# RTI-Dome-eth-RP2040_V2.net
KiCad netlist of a schematic drawn in EAGLE
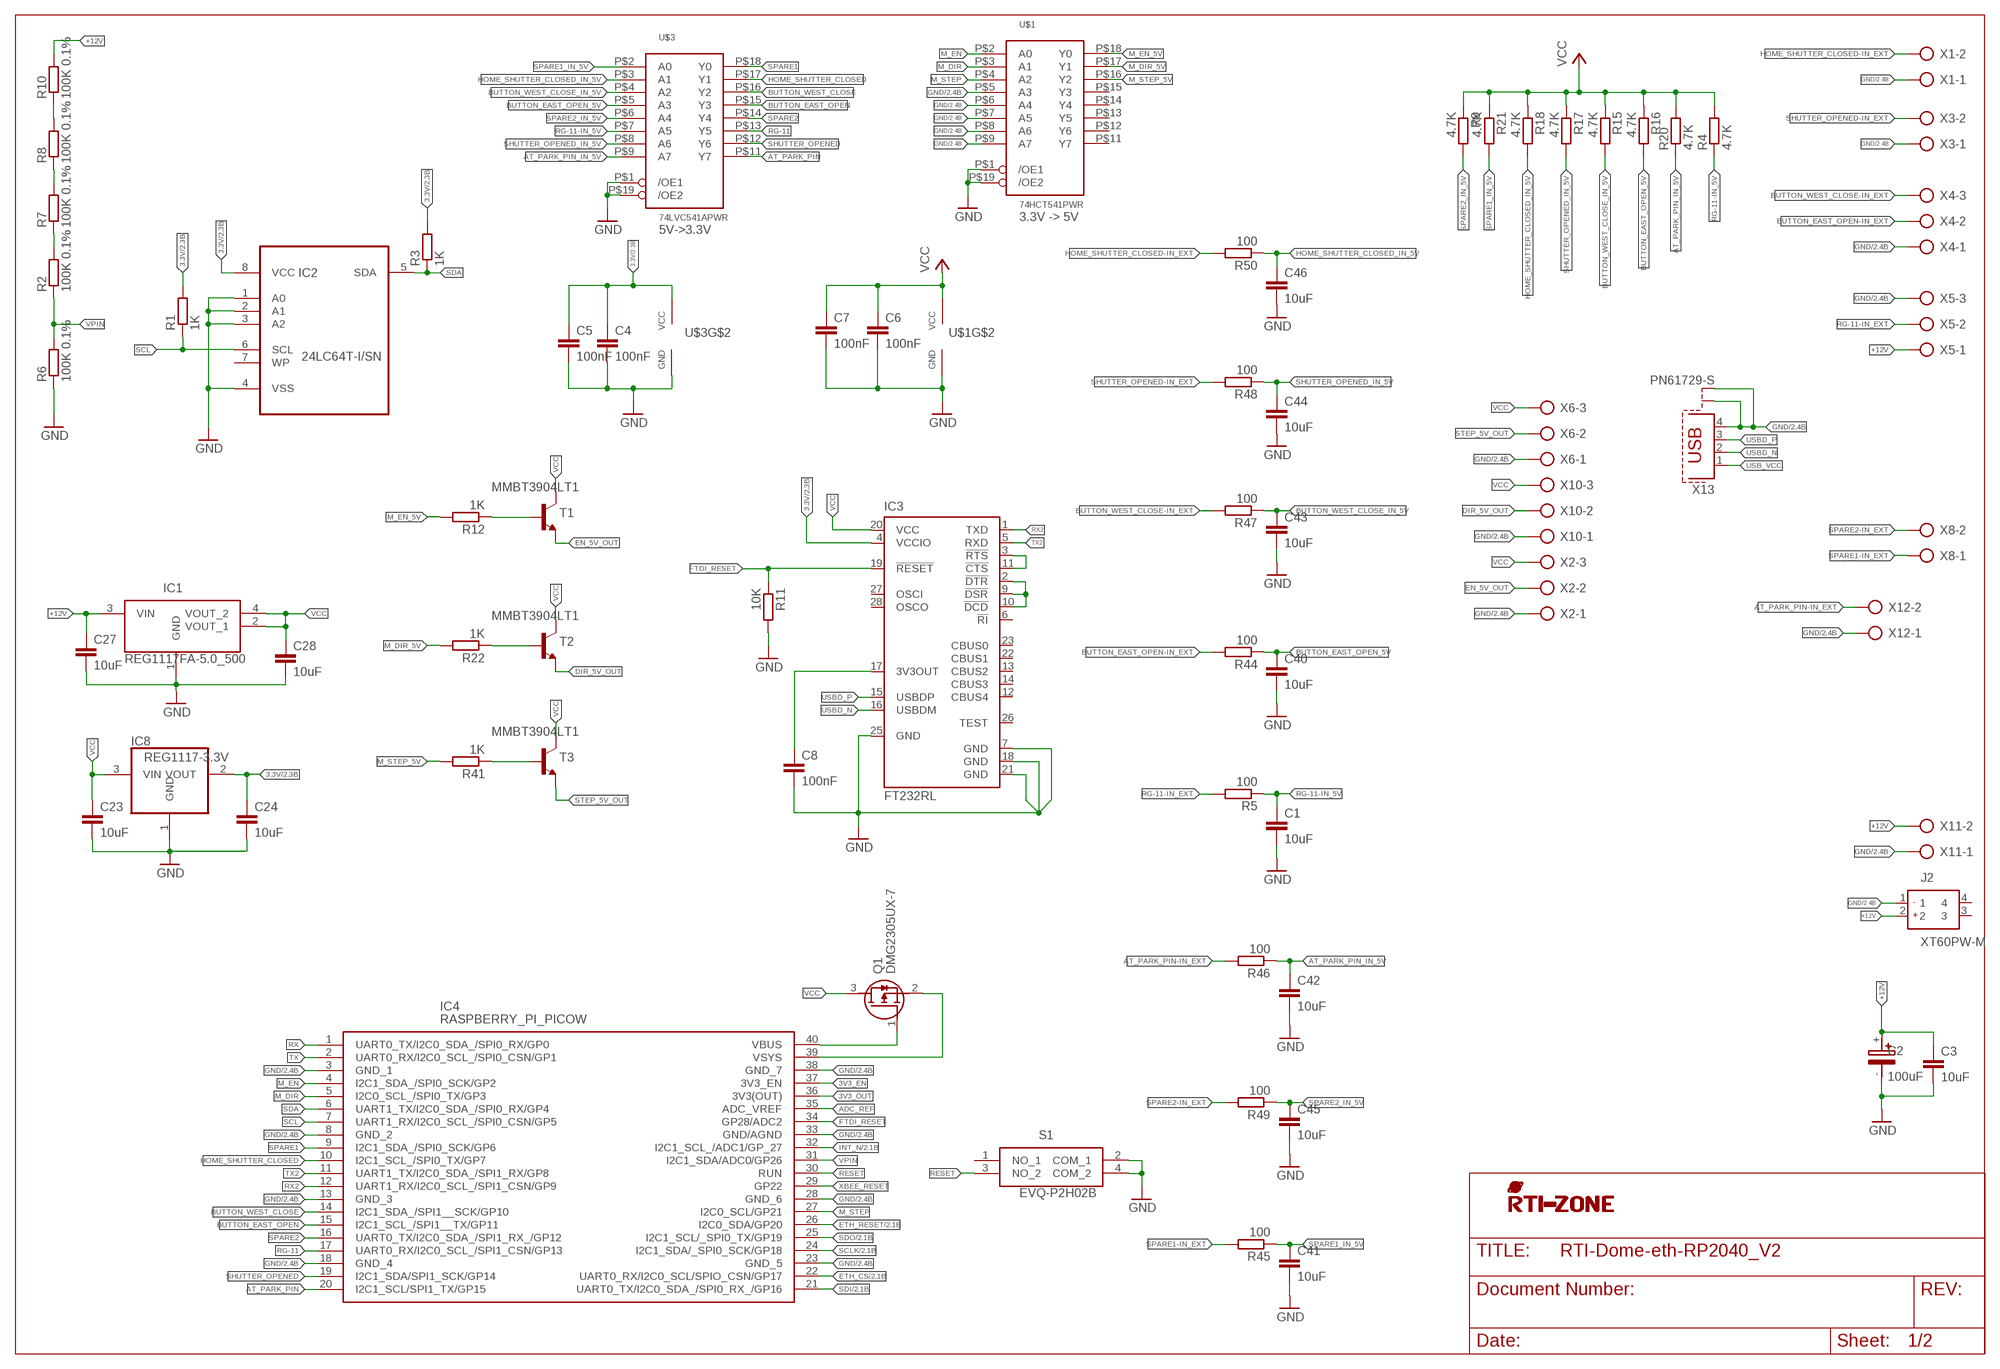
[diagram p0: schematic, sheet 1]
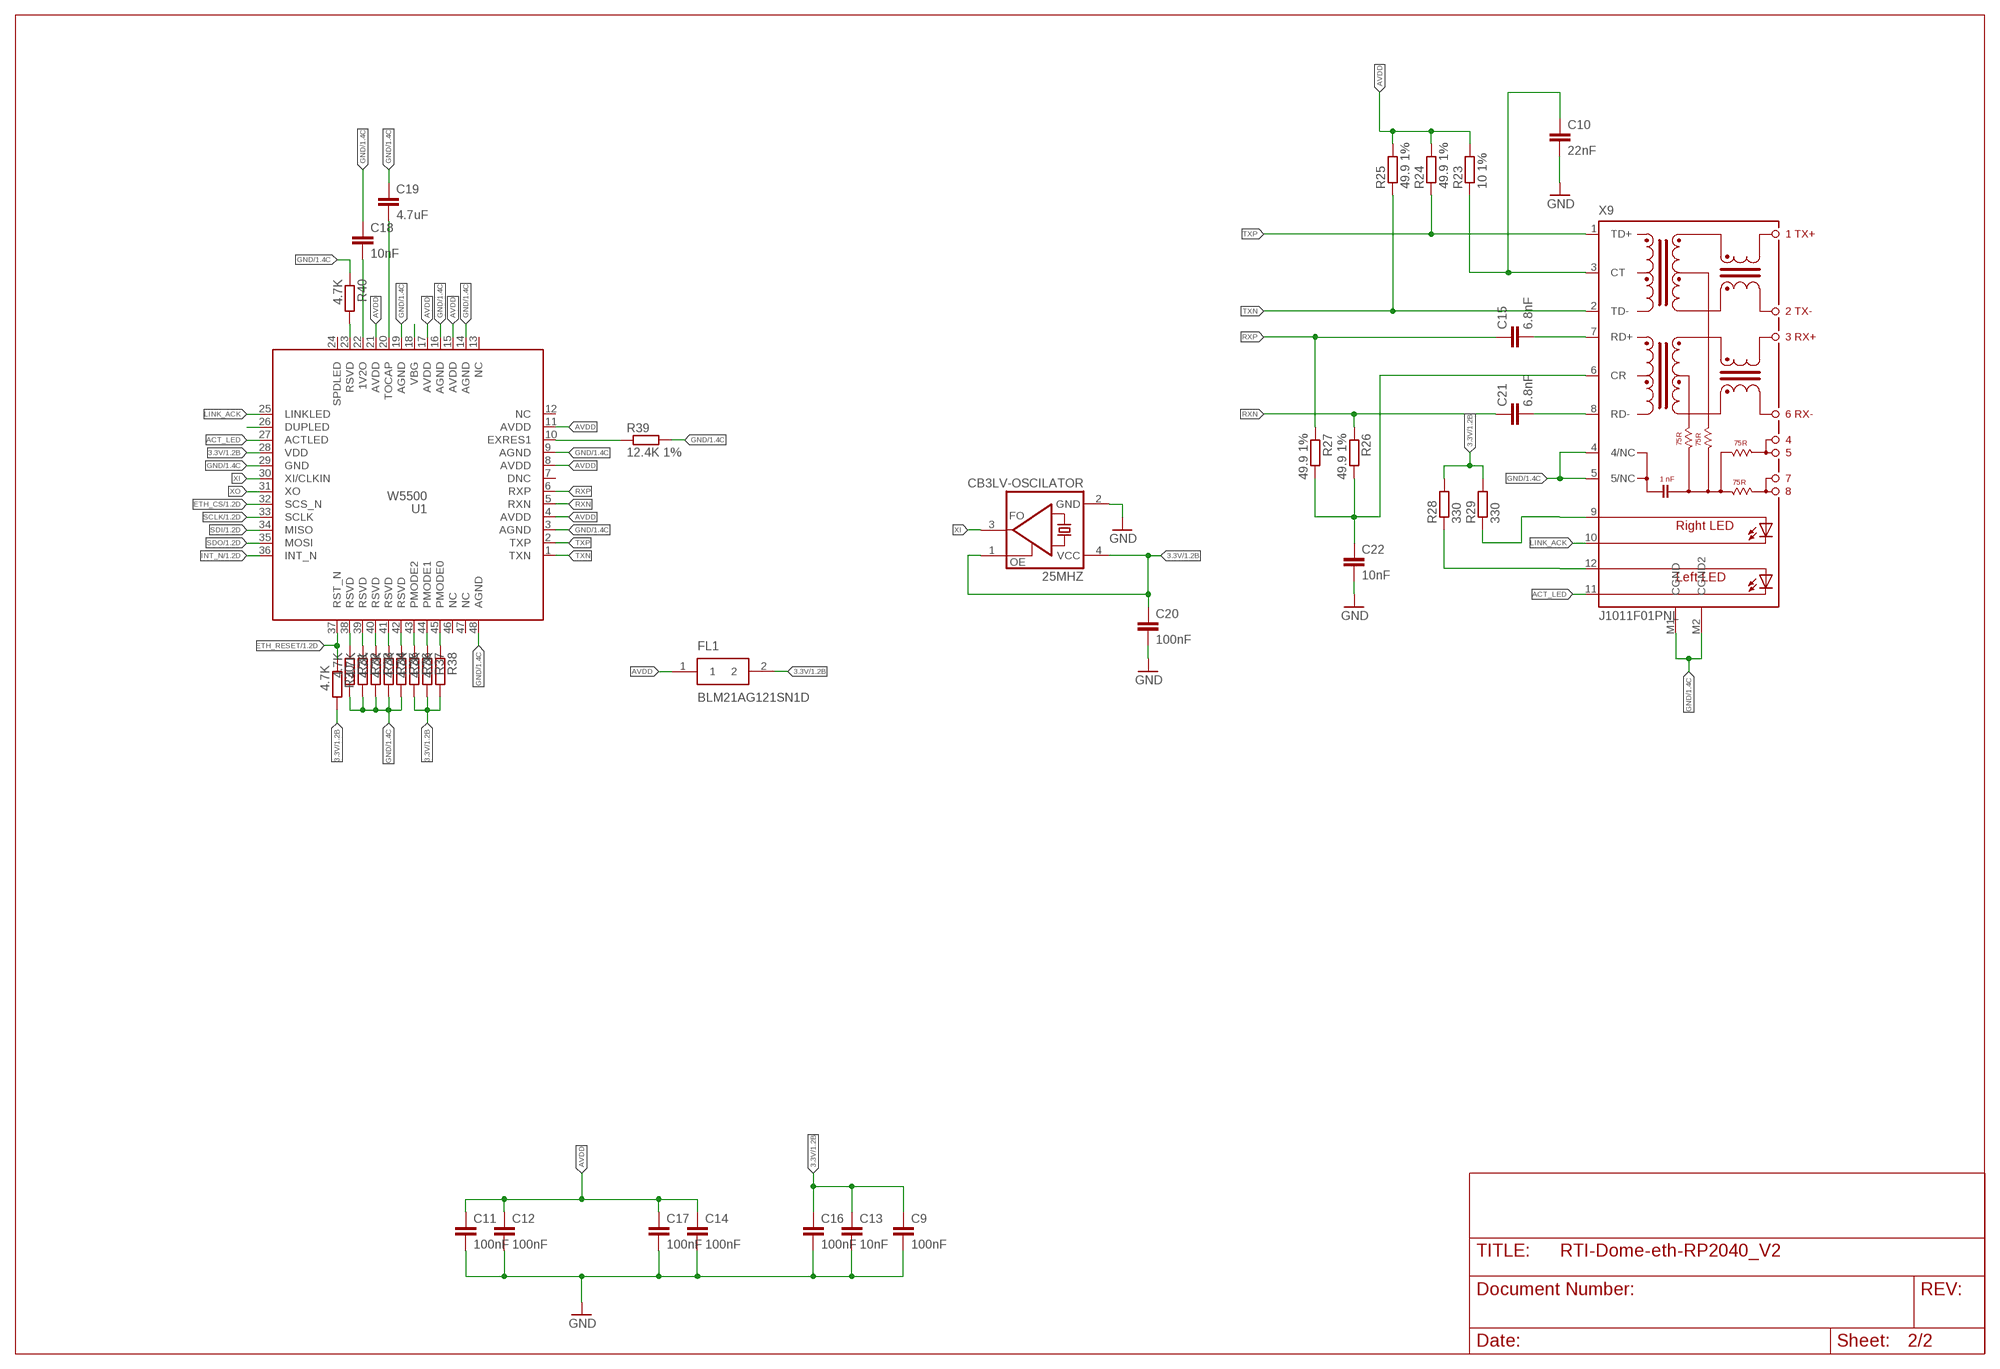
[diagram p1: schematic, sheet 2]

(export (version "E")
  (design (tool "Eeschema 10.0.6"))
  (components
    (comp (ref "C1")
      (value "10uF")
      (footprint "eagle-import:C0603")
      (fields (field (name "MPN") "CC0805KKX5R8BB106"))
      (libsource (lib "eagle-import") (part "C-EUC0603"))
    )
    (comp (ref "C2")
      (value "100uF")
      (footprint "eagle-import:UD-10X10_NICHICON")
      (fields (field (name "MPN") "MAL215099804E3"))
      (libsource (lib "eagle-import") (part "MAL215099804E3{dblquote}{dblquote}"))
    )
    (comp (ref "C3")
      (value "10uF")
      (footprint "eagle-import:C0603")
      (fields (field (name "MPN") "CC0805KKX5R8BB106"))
      (libsource (lib "eagle-import") (part "C-EUC0603"))
    )
    (comp (ref "C4")
      (value "100nF")
      (footprint "eagle-import:C0603")
      (fields (field (name "MPN") "0805YD104KAT2A"))
      (libsource (lib "eagle-import") (part "C-EUC0603"))
    )
    (comp (ref "C5")
      (value "100nF")
      (footprint "eagle-import:C0603")
      (fields (field (name "MPN") "0805YD104KAT2A"))
      (libsource (lib "eagle-import") (part "C-EUC0603"))
    )
    (comp (ref "C6")
      (value "100nF")
      (footprint "eagle-import:C0603")
      (fields (field (name "MPN") "0805YD104KAT2A"))
      (libsource (lib "eagle-import") (part "C-EUC0603"))
    )
    (comp (ref "C7")
      (value "100nF")
      (footprint "eagle-import:C0603")
      (fields (field (name "MPN") "0805YD104KAT2A"))
      (libsource (lib "eagle-import") (part "C-EUC0603"))
    )
    (comp (ref "C8")
      (value "100nF")
      (footprint "eagle-import:C0603")
      (fields (field (name "MPN") "0805YD104KAT2A"))
      (libsource (lib "eagle-import") (part "C-EUC0603"))
    )
    (comp (ref "C23")
      (value "10uF")
      (footprint "eagle-import:C0603")
      (fields (field (name "MPN") "CC0805KKX5R8BB106"))
      (libsource (lib "eagle-import") (part "C-EUC0603"))
    )
    (comp (ref "C24")
      (value "10uF")
      (footprint "eagle-import:C0603")
      (fields (field (name "MPN") "CC0805KKX5R8BB106"))
      (libsource (lib "eagle-import") (part "C-EUC0603"))
    )
    (comp (ref "C27")
      (value "10uF")
      (footprint "eagle-import:C0603")
      (fields (field (name "MPN") "CC0805KKX5R8BB106"))
      (libsource (lib "eagle-import") (part "C-EUC0603"))
    )
    (comp (ref "C28")
      (value "10uF")
      (footprint "eagle-import:C0603")
      (fields (field (name "MPN") "CC0805KKX5R8BB106"))
      (libsource (lib "eagle-import") (part "C-EUC0603"))
    )
    (comp (ref "C40")
      (value "10uF")
      (footprint "eagle-import:C0603")
      (fields (field (name "MPN") "CC0805KKX5R8BB106"))
      (libsource (lib "eagle-import") (part "C-EUC0603"))
    )
    (comp (ref "C41")
      (value "10uF")
      (footprint "eagle-import:C0603")
      (fields (field (name "MPN") "CC0805KKX5R8BB106"))
      (libsource (lib "eagle-import") (part "C-EUC0603"))
    )
    (comp (ref "C42")
      (value "10uF")
      (footprint "eagle-import:C0603")
      (fields (field (name "MPN") "CC0805KKX5R8BB106"))
      (libsource (lib "eagle-import") (part "C-EUC0603"))
    )
    (comp (ref "C43")
      (value "10uF")
      (footprint "eagle-import:C0603")
      (fields (field (name "MPN") "CC0805KKX5R8BB106"))
      (libsource (lib "eagle-import") (part "C-EUC0603"))
    )
    (comp (ref "C44")
      (value "10uF")
      (footprint "eagle-import:C0603")
      (fields (field (name "MPN") "CC0805KKX5R8BB106"))
      (libsource (lib "eagle-import") (part "C-EUC0603"))
    )
    (comp (ref "C45")
      (value "10uF")
      (footprint "eagle-import:C0603")
      (fields (field (name "MPN") "CC0805KKX5R8BB106"))
      (libsource (lib "eagle-import") (part "C-EUC0603"))
    )
    (comp (ref "C46")
      (value "10uF")
      (footprint "eagle-import:C0603")
      (fields (field (name "MPN") "CC0805KKX5R8BB106"))
      (libsource (lib "eagle-import") (part "C-EUC0603"))
    )
    (comp (ref "IC1")
      (value "REG1117FA-5.0_500")
      (footprint "eagle-import:REG1117FA50500")
      (fields
        (field (name "ARROW_PART_NUMBER") "REG1117FA-5.0/500")
        (field (name "MOUSER_PART_NUMBER") "595-REG1117FA50/500")
      )
      (libsource (lib "eagle-import") (part "REG1117FA-5.0_500"))
    )
    (comp (ref "IC2")
      (value "24LC64T-I/SN")
      (footprint "eagle-import:SOIC127P600X175-8N")
      (libsource (lib "eagle-import") (part "24LC64T-I/SN"))
    )
    (comp (ref "IC3")
      (value "FT232RL")
      (footprint "eagle-import:SSOP28")
      (fields (field (name "MPN") "FT232RL-REEL"))
      (libsource (lib "eagle-import") (part "FT232RL"))
    )
    (comp (ref "IC4")
      (value "RASPBERRY_PI_PICOW")
      (footprint "eagle-import:RASPBERRYPIPICO-W")
      (libsource (lib "eagle-import") (part "RASPBERRY_PI_PICOW"))
    )
    (comp (ref "IC8")
      (value "REG1117-3.3V")
      (footprint "eagle-import:SOT223")
      (fields (field (name "MPN") "REG1117") (field (name "MPN_1") "REG1117-3.3/2K5"))
      (libsource (lib "eagle-import") (part "REG1117"))
    )
    (comp (ref "J2")
      (value "XT60PW-M")
      (footprint "eagle-import:XT60PWM")
      (libsource (lib "eagle-import") (part "XT60PW-M"))
    )
    (comp (ref "Q1")
      (value "DMG2305UX-7")
      (footprint "eagle-import:SOT96P240X115-3N")
      (fields (field (name "MOUSER_PART_NUMBER") "621-DMG2305UX-7"))
      (libsource (lib "eagle-import") (part "DMG2305UX-7"))
    )
    (comp (ref "R1")
      (value "1K")
      (footprint "eagle-import:R0603")
      (fields (field (name "MPN") "RT0805FRE071KL"))
      (libsource (lib "eagle-import") (part "R-EU_R0603"))
    )
    (comp (ref "R2")
      (value "100K 0.1%")
      (footprint "eagle-import:R0603")
      (fields (field (name "MPN") "AT0805BRD07100KL"))
      (libsource (lib "eagle-import") (part "R-EU_R0603"))
    )
    (comp (ref "R3")
      (value "1K")
      (footprint "eagle-import:R0603")
      (fields (field (name "MPN") "RT0805FRE071KL"))
      (libsource (lib "eagle-import") (part "R-EU_R0603"))
    )
    (comp (ref "R4")
      (value "4.7K")
      (footprint "eagle-import:R0603")
      (fields (field (name "MPN") "RT0805FRE074K7L"))
      (libsource (lib "eagle-import") (part "R-EU_R0603"))
    )
    (comp (ref "R5")
      (value "100")
      (footprint "eagle-import:R0603")
      (fields (field (name "MPN") "RT0805FRD07100RL"))
      (libsource (lib "eagle-import") (part "R-EU_R0603"))
    )
    (comp (ref "R6")
      (value "100K 0.1%")
      (footprint "eagle-import:R0603")
      (fields (field (name "MPN") "AT0805BRD07100KL"))
      (libsource (lib "eagle-import") (part "R-EU_R0603"))
    )
    (comp (ref "R7")
      (value "100K 0.1%")
      (footprint "eagle-import:R0603")
      (fields (field (name "MPN") "AT0805BRD07100KL"))
      (libsource (lib "eagle-import") (part "R-EU_R0603"))
    )
    (comp (ref "R8")
      (value "100K 0.1%")
      (footprint "eagle-import:R0603")
      (fields (field (name "MPN") "AT0805BRD07100KL"))
      (libsource (lib "eagle-import") (part "R-EU_R0603"))
    )
    (comp (ref "R9")
      (value "4.7K")
      (footprint "eagle-import:R0603")
      (fields (field (name "MPN") "RT0805FRE074K7L"))
      (libsource (lib "eagle-import") (part "R-EU_R0603"))
    )
    (comp (ref "R10")
      (value "100K 0.1%")
      (footprint "eagle-import:R0603")
      (fields (field (name "MPN") "AT0805BRD07100KL"))
      (libsource (lib "eagle-import") (part "R-EU_R0603"))
    )
    (comp (ref "R11")
      (value "10K")
      (footprint "eagle-import:R0603")
      (fields (field (name "MPN") "RT0805FRE0710KL"))
      (libsource (lib "eagle-import") (part "R-EU_R0603"))
    )
    (comp (ref "R12")
      (value "1K")
      (footprint "eagle-import:R0603")
      (fields (field (name "MPN") "RT0805FRE074K7L"))
      (libsource (lib "eagle-import") (part "R-EU_R0603"))
    )
    (comp (ref "R15")
      (value "4.7K")
      (footprint "eagle-import:R0603")
      (fields (field (name "MPN") "RT0805FRE074K7L"))
      (libsource (lib "eagle-import") (part "R-EU_R0603"))
    )
    (comp (ref "R16")
      (value "4.7K")
      (footprint "eagle-import:R0603")
      (fields (field (name "MPN") "RT0805FRE074K7L"))
      (libsource (lib "eagle-import") (part "R-EU_R0603"))
    )
    (comp (ref "R17")
      (value "4.7K")
      (footprint "eagle-import:R0603")
      (fields (field (name "MPN") "RT0805FRE074K7L"))
      (libsource (lib "eagle-import") (part "R-EU_R0603"))
    )
    (comp (ref "R18")
      (value "4.7K")
      (footprint "eagle-import:R0603")
      (fields (field (name "MPN") "RT0805FRE074K7L"))
      (libsource (lib "eagle-import") (part "R-EU_R0603"))
    )
    (comp (ref "R20")
      (value "4.7K")
      (footprint "eagle-import:R0603")
      (fields (field (name "MPN") "RT0805FRE074K7L"))
      (libsource (lib "eagle-import") (part "R-EU_R0603"))
    )
    (comp (ref "R21")
      (value "4.7K")
      (footprint "eagle-import:R0603")
      (fields (field (name "MPN") "RT0805FRE074K7L"))
      (libsource (lib "eagle-import") (part "R-EU_R0603"))
    )
    (comp (ref "R22")
      (value "1K")
      (footprint "eagle-import:R0603")
      (fields (field (name "MPN") "RT0805FRE074K7L"))
      (libsource (lib "eagle-import") (part "R-EU_R0603"))
    )
    (comp (ref "R41")
      (value "1K")
      (footprint "eagle-import:R0603")
      (fields (field (name "MPN") "RT0805FRE074K7L"))
      (libsource (lib "eagle-import") (part "R-EU_R0603"))
    )
    (comp (ref "R44")
      (value "100")
      (footprint "eagle-import:R0603")
      (fields (field (name "MPN") "RT0805FRD07100RL"))
      (libsource (lib "eagle-import") (part "R-EU_R0603"))
    )
    (comp (ref "R45")
      (value "100")
      (footprint "eagle-import:R0603")
      (fields (field (name "MPN") "RT0805FRD07100RL"))
      (libsource (lib "eagle-import") (part "R-EU_R0603"))
    )
    (comp (ref "R46")
      (value "100")
      (footprint "eagle-import:R0603")
      (fields (field (name "MPN") "RT0805FRD07100RL"))
      (libsource (lib "eagle-import") (part "R-EU_R0603"))
    )
    (comp (ref "R47")
      (value "100")
      (footprint "eagle-import:R0603")
      (fields (field (name "MPN") "RT0805FRD07100RL"))
      (libsource (lib "eagle-import") (part "R-EU_R0603"))
    )
    (comp (ref "R48")
      (value "100")
      (footprint "eagle-import:R0603")
      (fields (field (name "MPN") "RT0805FRD07100RL"))
      (libsource (lib "eagle-import") (part "R-EU_R0603"))
    )
    (comp (ref "R49")
      (value "100")
      (footprint "eagle-import:R0603")
      (fields (field (name "MPN") "RT0805FRD07100RL"))
      (libsource (lib "eagle-import") (part "R-EU_R0603"))
    )
    (comp (ref "R50")
      (value "100")
      (footprint "eagle-import:R0603")
      (fields (field (name "MPN") "RT0805FRD07100RL"))
      (libsource (lib "eagle-import") (part "R-EU_R0603"))
    )
    (comp (ref "S1")
      (value "EVQ-P2H02B")
      (footprint "eagle-import:EVQP2H02B")
      (fields (field (name "MOUSER_PART_NUMBER") "667-EVQ-P2H02B"))
      (libsource (lib "eagle-import") (part "EVQ-P2H02B"))
    )
    (comp (ref "T1")
      (value "MMBT3904LT1")
      (footprint "eagle-import:SOT23")
      (libsource (lib "eagle-import") (part "MMBT3904LT1"))
    )
    (comp (ref "T2")
      (value "MMBT3904LT1")
      (footprint "eagle-import:SOT23")
      (libsource (lib "eagle-import") (part "MMBT3904LT1"))
    )
    (comp (ref "T3")
      (value "MMBT3904LT1")
      (footprint "eagle-import:SOT23")
      (libsource (lib "eagle-import") (part "MMBT3904LT1"))
    )
    (comp (ref "U$1")
      (value "74HCT541PWR")
      (footprint "eagle-import:TSSOP20")
      (libsource (lib "eagle-import") (part "74541B"))
    )
    (comp (ref "U$3")
      (value "74LVC541APWR")
      (footprint "eagle-import:TSSOP20")
      (libsource (lib "eagle-import") (part "74541B"))
    )
    (comp (ref "U$4")
      (value "RTI-LOGO_BIG")
      (footprint "eagle-import:LOGO_BIG")
      (libsource (lib "eagle-import") (part "RTI-LOGO_BIG"))
    )
    (comp (ref "X1")
      (value "AK500/2")
      (footprint "eagle-import:AK500_2")
      (fields (field (name "MPN") "691101710002"))
      (libsource (lib "eagle-import") (part "AK500/2"))
    )
    (comp (ref "X2")
      (value "AK500/3")
      (footprint "eagle-import:AK500_3")
      (libsource (lib "eagle-import") (part "AK500/3"))
    )
    (comp (ref "X3")
      (value "AK500/2")
      (footprint "eagle-import:AK500_2")
      (fields (field (name "MPN") "691101710002"))
      (libsource (lib "eagle-import") (part "AK500/2"))
    )
    (comp (ref "X4")
      (value "AK500/3")
      (footprint "eagle-import:AK500_3")
      (fields (field (name "MPN") "691101710003"))
      (libsource (lib "eagle-import") (part "AK500/3"))
    )
    (comp (ref "X5")
      (value "AK500/3")
      (footprint "eagle-import:AK500_3")
      (fields (field (name "MPN") "691101710003"))
      (libsource (lib "eagle-import") (part "AK500/3"))
    )
    (comp (ref "X6")
      (value "AK500/3")
      (footprint "eagle-import:AK500_3")
      (libsource (lib "eagle-import") (part "AK500/3"))
    )
    (comp (ref "X8")
      (value "AK500/2")
      (footprint "eagle-import:AK500_2")
      (fields (field (name "MPN") "691101710002"))
      (libsource (lib "eagle-import") (part "AK500/2"))
    )
    (comp (ref "X10")
      (value "AK500/3")
      (footprint "eagle-import:AK500_3")
      (libsource (lib "eagle-import") (part "AK500/3"))
    )
    (comp (ref "X11")
      (value "AK500/2")
      (footprint "eagle-import:AK500_2")
      (fields (field (name "MPN") "691101710002"))
      (libsource (lib "eagle-import") (part "AK500/2"))
    )
    (comp (ref "X12")
      (value "AK500/2")
      (footprint "eagle-import:AK500_2")
      (fields (field (name "MPN") "691101710002"))
      (libsource (lib "eagle-import") (part "AK500/2"))
    )
    (comp (ref "X13")
      (value "PN61729-S")
      (footprint "eagle-import:PN61729-S")
      (fields (field (name "MPN") "SS-52300-001"))
      (libsource (lib "eagle-import") (part "PN61729-S"))
    )
    (comp (ref "25MHZ")
      (value "CB3LV-OSCILATOR")
      (footprint "eagle-import:SMD-7050_4P")
      (fields (field (name "MPN") "CB3LV-3I-25M0000"))
      (libsource (lib "eagle-import") (part "CB3LV-OSCILATOR"))
    )
    (comp (ref "C9")
      (value "100nF")
      (footprint "eagle-import:C0603")
      (fields (field (name "MPN") "0805YD104KAT2A"))
      (libsource (lib "eagle-import") (part "C-EUC0603"))
    )
    (comp (ref "C10")
      (value "22nF")
      (footprint "eagle-import:C0603")
      (fields (field (name "MPN") "CC0805JRX7R8BB223"))
      (libsource (lib "eagle-import") (part "C-EUC0603"))
    )
    (comp (ref "C11")
      (value "100nF")
      (footprint "eagle-import:C0603")
      (fields (field (name "MPN") "0805YD104KAT2A"))
      (libsource (lib "eagle-import") (part "C-EUC0603"))
    )
    (comp (ref "C12")
      (value "100nF")
      (footprint "eagle-import:C0603")
      (fields (field (name "MPN") "0805YD104KAT2A"))
      (libsource (lib "eagle-import") (part "C-EUC0603"))
    )
    (comp (ref "C13")
      (value "10nF")
      (footprint "eagle-import:C0603")
      (fields (field (name "MPN") " CC0805KRX7R9BB103"))
      (libsource (lib "eagle-import") (part "C-EUC0603"))
    )
    (comp (ref "C14")
      (value "100nF")
      (footprint "eagle-import:C0603")
      (fields (field (name "MPN") "0805YD104KAT2A"))
      (libsource (lib "eagle-import") (part "C-EUC0603"))
    )
    (comp (ref "C15")
      (value "6.8nF")
      (footprint "eagle-import:C0603")
      (fields (field (name "MPN") "C0805C682F4HACTU"))
      (libsource (lib "eagle-import") (part "C-EUC0603"))
    )
    (comp (ref "C16")
      (value "100nF")
      (footprint "eagle-import:C0603")
      (fields (field (name "MPN") "0805YD104KAT2A"))
      (libsource (lib "eagle-import") (part "C-EUC0603"))
    )
    (comp (ref "C17")
      (value "100nF")
      (footprint "eagle-import:C0603")
      (fields (field (name "MPN") "0805YD104KAT2A"))
      (libsource (lib "eagle-import") (part "C-EUC0603"))
    )
    (comp (ref "C18")
      (value "10nF")
      (footprint "eagle-import:C0603")
      (fields (field (name "MPN") " CC0805KRX7R9BB103"))
      (libsource (lib "eagle-import") (part "C-EUC0603"))
    )
    (comp (ref "C19")
      (value "4.7uF")
      (footprint "eagle-import:C0603")
      (fields (field (name "MPN") "C0805C475J3RACTU"))
      (libsource (lib "eagle-import") (part "C-EUC0603"))
    )
    (comp (ref "C20")
      (value "100nF")
      (footprint "eagle-import:C0603")
      (fields (field (name "MPN") "0805YD104KAT2A"))
      (libsource (lib "eagle-import") (part "C-EUC0603"))
    )
    (comp (ref "C21")
      (value "6.8nF")
      (footprint "eagle-import:C0603")
      (fields (field (name "MPN") "C0805C682F4HACTU"))
      (libsource (lib "eagle-import") (part "C-EUC0603"))
    )
    (comp (ref "C22")
      (value "10nF")
      (footprint "eagle-import:C0603")
      (fields (field (name "MPN") " CC0805KRX7R9BB103"))
      (libsource (lib "eagle-import") (part "C-EUC0603"))
    )
    (comp (ref "FL1")
      (value "BLM21AG121SN1D")
      (footprint "eagle-import:L0805")
      (libsource (lib "eagle-import") (part "BLM21AG121SN1D"))
    )
    (comp (ref "R23")
      (value "10 1%")
      (footprint "eagle-import:R0603")
      (fields (field (name "MPN") "RT0805FRE1310RL"))
      (libsource (lib "eagle-import") (part "R-EU_R0603"))
    )
    (comp (ref "R24")
      (value "49.9 1%")
      (footprint "eagle-import:R0603")
      (fields (field (name "MPN") "RC0805FR-0749R9L"))
      (libsource (lib "eagle-import") (part "R-EU_R0603"))
    )
    (comp (ref "R25")
      (value "49.9 1%")
      (footprint "eagle-import:R0603")
      (fields (field (name "MPN") "RC0805FR-0749R9L"))
      (libsource (lib "eagle-import") (part "R-EU_R0603"))
    )
    (comp (ref "R26")
      (value "49.9 1%")
      (footprint "eagle-import:R0603")
      (fields (field (name "MPN") "RC0805FR-0749R9L"))
      (libsource (lib "eagle-import") (part "R-EU_R0603"))
    )
    (comp (ref "R27")
      (value "49.9 1%")
      (footprint "eagle-import:R0603")
      (fields (field (name "MPN") "RC0805FR-0749R9L"))
      (libsource (lib "eagle-import") (part "R-EU_R0603"))
    )
    (comp (ref "R28")
      (value "330")
      (footprint "eagle-import:R0603")
      (fields (field (name "MPN") " RC0805JR-07330RL"))
      (libsource (lib "eagle-import") (part "R-EU_R0603"))
    )
    (comp (ref "R29")
      (value "330")
      (footprint "eagle-import:R0603")
      (fields (field (name "MPN") " RC0805JR-07330RL"))
      (libsource (lib "eagle-import") (part "R-EU_R0603"))
    )
    (comp (ref "R30")
      (value "4.7K")
      (footprint "eagle-import:R0603")
      (fields (field (name "MPN") "RT0805FRE074K7L"))
      (libsource (lib "eagle-import") (part "R-EU_R0603"))
    )
    (comp (ref "R31")
      (value "4.7K")
      (footprint "eagle-import:R0603")
      (fields (field (name "MPN") "RT0805FRE074K7L"))
      (libsource (lib "eagle-import") (part "R-EU_R0603"))
    )
    (comp (ref "R32")
      (value "4.7K")
      (footprint "eagle-import:R0603")
      (fields (field (name "MPN") "RT0805FRE074K7L"))
      (libsource (lib "eagle-import") (part "R-EU_R0603"))
    )
    (comp (ref "R33")
      (value "4.7K")
      (footprint "eagle-import:R0603")
      (fields (field (name "MPN") "RT0805FRE074K7L"))
      (libsource (lib "eagle-import") (part "R-EU_R0603"))
    )
    (comp (ref "R34")
      (value "4.7K")
      (footprint "eagle-import:R0603")
      (fields (field (name "MPN") "RT0805FRE074K7L"))
      (libsource (lib "eagle-import") (part "R-EU_R0603"))
    )
    (comp (ref "R35")
      (value "4.7K")
      (footprint "eagle-import:R0603")
      (fields (field (name "MPN") "RT0805FRE074K7L"))
      (libsource (lib "eagle-import") (part "R-EU_R0603"))
    )
    (comp (ref "R36")
      (value "4.7K")
      (footprint "eagle-import:R0603")
      (fields (field (name "MPN") "RT0805FRE074K7L"))
      (libsource (lib "eagle-import") (part "R-EU_R0603"))
    )
    (comp (ref "R37")
      (value "4.7K")
      (footprint "eagle-import:R0603")
      (fields (field (name "MPN") "RT0805FRE074K7L"))
      (libsource (lib "eagle-import") (part "R-EU_R0603"))
    )
    (comp (ref "R38")
      (value "4.7K")
      (footprint "eagle-import:R0603")
      (fields (field (name "MPN") "RT0805FRE074K7L"))
      (libsource (lib "eagle-import") (part "R-EU_R0603"))
    )
    (comp (ref "R39")
      (value "12.4K 1%")
      (footprint "eagle-import:R0603")
      (fields (field (name "MPN") "RC0805FR-0712K4L"))
      (libsource (lib "eagle-import") (part "R-EU_R0603"))
    )
    (comp (ref "R40")
      (value "4.7K")
      (footprint "eagle-import:R0603")
      (fields (field (name "MPN") "RT0805FRE074K7L"))
      (libsource (lib "eagle-import") (part "R-EU_R0603"))
    )
    (comp (ref "U1")
      (value "W5500")
      (footprint "eagle-import:LQFP48")
      (libsource (lib "eagle-import") (part "W5500"))
    )
    (comp (ref "X9")
      (value "J1011F01PNL")
      (footprint "eagle-import:J1011F01PNL")
      (libsource (lib "eagle-import") (part "J1011F01PNL"))
    )
  )
  (nets
    (net (code "1") (name "+12V") (class "Default")
      (node (ref "C2") (pin "+") (pinfunction "+_+") (pintype "bidirectional"))
      (node (ref "C27") (pin "1") (pinfunction "1_1") (pintype "passive"))
      (node (ref "C3") (pin "1") (pinfunction "1_1") (pintype "passive"))
      (node (ref "IC1") (pin "3") (pinfunction "VIN_3") (pintype "bidirectional"))
      (node (ref "J2") (pin "2") (pinfunction "2_2") (pintype "bidirectional"))
      (node (ref "R10") (pin "2") (pinfunction "2_2") (pintype "passive"))
      (node (ref "X11") (pin "2") (pinfunction "KL_2") (pintype "passive"))
      (node (ref "X5") (pin "1") (pinfunction "KL_1") (pintype "passive"))
    )
    (net (code "2") (name "3.3V") (class "Default")
      (node (ref "25MHZ") (pin "1") (pinfunction "OE_1") (pintype "input"))
      (node (ref "25MHZ") (pin "4") (pinfunction "VDD_4") (pintype "power_in"))
      (node (ref "C13") (pin "1") (pinfunction "1_1") (pintype "passive"))
      (node (ref "C16") (pin "1") (pinfunction "1_1") (pintype "passive"))
      (node (ref "C20") (pin "1") (pinfunction "1_1") (pintype "passive"))
      (node (ref "C24") (pin "1") (pinfunction "1_1") (pintype "passive"))
      (node (ref "C4") (pin "1") (pinfunction "1_1") (pintype "passive"))
      (node (ref "C5") (pin "1") (pinfunction "1_1") (pintype "passive"))
      (node (ref "C9") (pin "1") (pinfunction "1_1") (pintype "passive"))
      (node (ref "FL1") (pin "2") (pinfunction "2_2") (pintype "bidirectional"))
      (node (ref "IC2") (pin "8") (pinfunction "VCC_8") (pintype "power_in"))
      (node (ref "IC3") (pin "4") (pinfunction "VCCIO_4") (pintype "power_in"))
      (node (ref "IC8") (pin "2") (pinfunction "VOUT_2") (pintype "output"))
      (node (ref "R1") (pin "2") (pinfunction "2_2") (pintype "passive"))
      (node (ref "R28") (pin "2") (pinfunction "2_2") (pintype "passive"))
      (node (ref "R29") (pin "2") (pinfunction "2_2") (pintype "passive"))
      (node (ref "R3") (pin "2") (pinfunction "2_2") (pintype "passive"))
      (node (ref "R30") (pin "2") (pinfunction "2_2") (pintype "passive"))
      (node (ref "R36") (pin "2") (pinfunction "2_2") (pintype "passive"))
      (node (ref "R37") (pin "2") (pinfunction "2_2") (pintype "passive"))
      (node (ref "R38") (pin "2") (pinfunction "2_2") (pintype "passive"))
      (node (ref "U$3") (pin "P$20") (pinfunction "VCC_P$20") (pintype "power_in"))
      (node (ref "U1") (pin "28") (pinfunction "VDD_28") (pintype "passive"))
    )
    (net (code "3") (name "3V3_EN") (class "Default")
      (node (ref "IC4") (pin "37") (pinfunction "3V3_EN_37") (pintype "bidirectional"))
    )
    (net (code "4") (name "3V3_OUT") (class "Default")
      (node (ref "IC4") (pin "36") (pinfunction "3V3(OUT)_36") (pintype "bidirectional"))
    )
    (net (code "5") (name "ACT_LED") (class "Default")
      (node (ref "U1") (pin "27") (pinfunction "ACTLED_27") (pintype "passive"))
      (node (ref "X9") (pin "11") (pinfunction "C-L_11") (pintype "passive"))
    )
    (net (code "6") (name "ADC_REF") (class "Default")
      (node (ref "IC4") (pin "35") (pinfunction "ADC_VREF_35") (pintype "bidirectional"))
    )
    (net (code "7") (name "AT_PARK_PIN") (class "Default")
      (node (ref "IC4") (pin "20") (pinfunction "I2C1_SCL/SPI1_TX/GP15_20") (pintype "bidirectional"))
      (node (ref "U$3") (pin "P$11") (pinfunction "Y7_P$11") (pintype "output"))
    )
    (net (code "8") (name "AT_PARK_PIN-IN_EXT") (class "Default")
      (node (ref "R46") (pin "2") (pinfunction "2_2") (pintype "passive"))
      (node (ref "X12") (pin "2") (pinfunction "KL_2") (pintype "passive"))
    )
    (net (code "9") (name "AT_PARK_PIN_IN_5V") (class "Default")
      (node (ref "C42") (pin "1") (pinfunction "1_1") (pintype "passive"))
      (node (ref "R20") (pin "1") (pinfunction "1_1") (pintype "passive"))
      (node (ref "R46") (pin "1") (pinfunction "1_1") (pintype "passive"))
      (node (ref "U$3") (pin "P$9") (pinfunction "A7_P$9") (pintype "input"))
    )
    (net (code "10") (name "AVDD") (class "Default")
      (node (ref "C11") (pin "1") (pinfunction "1_1") (pintype "passive"))
      (node (ref "C12") (pin "1") (pinfunction "1_1") (pintype "passive"))
      (node (ref "C14") (pin "1") (pinfunction "1_1") (pintype "passive"))
      (node (ref "C17") (pin "1") (pinfunction "1_1") (pintype "passive"))
      (node (ref "FL1") (pin "1") (pinfunction "1_1") (pintype "bidirectional"))
      (node (ref "R23") (pin "2") (pinfunction "2_2") (pintype "passive"))
      (node (ref "R24") (pin "2") (pinfunction "2_2") (pintype "passive"))
      (node (ref "R25") (pin "2") (pinfunction "2_2") (pintype "passive"))
      (node (ref "U1") (pin "11") (pinfunction "AVDD_11") (pintype "passive"))
      (node (ref "U1") (pin "15") (pinfunction "AVDD_15") (pintype "passive"))
      (node (ref "U1") (pin "17") (pinfunction "AVDD_17") (pintype "passive"))
      (node (ref "U1") (pin "21") (pinfunction "AVDD_21") (pintype "passive"))
      (node (ref "U1") (pin "4") (pinfunction "AVDD_4") (pintype "passive"))
      (node (ref "U1") (pin "8") (pinfunction "AVDD_8") (pintype "passive"))
    )
    (net (code "11") (name "BUTTON_EAST_OPEN") (class "Default")
      (node (ref "IC4") (pin "15") (pinfunction "I2C1_SCL_/SPI1__TX/GP11_15") (pintype "bidirectional"))
      (node (ref "U$3") (pin "P$15") (pinfunction "Y3_P$15") (pintype "output"))
    )
    (net (code "12") (name "BUTTON_EAST_OPEN-IN_EXT") (class "Default")
      (node (ref "R44") (pin "2") (pinfunction "2_2") (pintype "passive"))
      (node (ref "X4") (pin "2") (pinfunction "KL_2") (pintype "passive"))
    )
    (net (code "13") (name "BUTTON_EAST_OPEN_5V") (class "Default")
      (node (ref "C40") (pin "1") (pinfunction "1_1") (pintype "passive"))
      (node (ref "R16") (pin "2") (pinfunction "2_2") (pintype "passive"))
      (node (ref "R44") (pin "1") (pinfunction "1_1") (pintype "passive"))
      (node (ref "U$3") (pin "P$5") (pinfunction "A3_P$5") (pintype "input"))
    )
    (net (code "14") (name "BUTTON_WEST_CLOSE") (class "Default")
      (node (ref "IC4") (pin "14") (pinfunction "I2C1_SDA_/SPI1__SCK/GP10_14") (pintype "bidirectional"))
      (node (ref "U$3") (pin "P$16") (pinfunction "Y2_P$16") (pintype "output"))
    )
    (net (code "15") (name "BUTTON_WEST_CLOSE-IN_EXT") (class "Default")
      (node (ref "R47") (pin "2") (pinfunction "2_2") (pintype "passive"))
      (node (ref "X4") (pin "3") (pinfunction "KL_3") (pintype "passive"))
    )
    (net (code "16") (name "BUTTON_WEST_CLOSE_IN_5V") (class "Default")
      (node (ref "C43") (pin "1") (pinfunction "1_1") (pintype "passive"))
      (node (ref "R15") (pin "2") (pinfunction "2_2") (pintype "passive"))
      (node (ref "R47") (pin "1") (pinfunction "1_1") (pintype "passive"))
      (node (ref "U$3") (pin "P$4") (pinfunction "A2_P$4") (pintype "input"))
    )
    (net (code "17") (name "DIR_5V_OUT") (class "Default")
      (node (ref "T2") (pin "2") (pinfunction "E_2") (pintype "passive"))
      (node (ref "X10") (pin "2") (pinfunction "KL_2") (pintype "passive"))
    )
    (net (code "18") (name "EN_5V_OUT") (class "Default")
      (node (ref "T1") (pin "2") (pinfunction "E_2") (pintype "passive"))
      (node (ref "X2") (pin "2") (pinfunction "KL_2") (pintype "passive"))
    )
    (net (code "19") (name "ETH_CS") (class "Default")
      (node (ref "IC4") (pin "22") (pinfunction "UART0_RX/I2C0_SCL/SPIO_CSN/GP17_22") (pintype "bidirectional"))
      (node (ref "U1") (pin "32") (pinfunction "SCS_N_32") (pintype "passive"))
    )
    (net (code "20") (name "ETH_RESET") (class "Default")
      (node (ref "IC4") (pin "26") (pinfunction "I2C0_SDA/GP20_26") (pintype "bidirectional"))
      (node (ref "R30") (pin "1") (pinfunction "1_1") (pintype "passive"))
      (node (ref "U1") (pin "37") (pinfunction "RST_N_37") (pintype "passive"))
    )
    (net (code "21") (name "FTDI_RESET") (class "Default")
      (node (ref "IC3") (pin "19") (pinfunction "~{RESET}_19") (pintype "input"))
      (node (ref "IC4") (pin "34") (pinfunction "GP28/ADC2_34") (pintype "bidirectional"))
      (node (ref "R11") (pin "1") (pinfunction "1_1") (pintype "passive"))
    )
    (net (code "22") (name "GND") (class "Default")
      (node (ref "25MHZ") (pin "2") (pinfunction "GND_2") (pintype "power_in"))
      (node (ref "C1") (pin "2") (pinfunction "2_2") (pintype "passive"))
      (node (ref "C10") (pin "2") (pinfunction "2_2") (pintype "passive"))
      (node (ref "C11") (pin "2") (pinfunction "2_2") (pintype "passive"))
      (node (ref "C12") (pin "2") (pinfunction "2_2") (pintype "passive"))
      (node (ref "C13") (pin "2") (pinfunction "2_2") (pintype "passive"))
      (node (ref "C14") (pin "2") (pinfunction "2_2") (pintype "passive"))
      (node (ref "C16") (pin "2") (pinfunction "2_2") (pintype "passive"))
      (node (ref "C17") (pin "2") (pinfunction "2_2") (pintype "passive"))
      (node (ref "C18") (pin "1") (pinfunction "1_1") (pintype "passive"))
      (node (ref "C19") (pin "1") (pinfunction "1_1") (pintype "passive"))
      (node (ref "C2") (pin "-") (pinfunction "-_-") (pintype "bidirectional"))
      (node (ref "C20") (pin "2") (pinfunction "2_2") (pintype "passive"))
      (node (ref "C22") (pin "2") (pinfunction "2_2") (pintype "passive"))
      (node (ref "C23") (pin "2") (pinfunction "2_2") (pintype "passive"))
      (node (ref "C24") (pin "2") (pinfunction "2_2") (pintype "passive"))
      (node (ref "C27") (pin "2") (pinfunction "2_2") (pintype "passive"))
      (node (ref "C28") (pin "2") (pinfunction "2_2") (pintype "passive"))
      (node (ref "C3") (pin "2") (pinfunction "2_2") (pintype "passive"))
      (node (ref "C4") (pin "2") (pinfunction "2_2") (pintype "passive"))
      (node (ref "C40") (pin "2") (pinfunction "2_2") (pintype "passive"))
      (node (ref "C41") (pin "2") (pinfunction "2_2") (pintype "passive"))
      (node (ref "C42") (pin "2") (pinfunction "2_2") (pintype "passive"))
      (node (ref "C43") (pin "2") (pinfunction "2_2") (pintype "passive"))
      (node (ref "C44") (pin "2") (pinfunction "2_2") (pintype "passive"))
      (node (ref "C45") (pin "2") (pinfunction "2_2") (pintype "passive"))
      (node (ref "C46") (pin "2") (pinfunction "2_2") (pintype "passive"))
      (node (ref "C5") (pin "2") (pinfunction "2_2") (pintype "passive"))
      (node (ref "C6") (pin "2") (pinfunction "2_2") (pintype "passive"))
      (node (ref "C7") (pin "2") (pinfunction "2_2") (pintype "passive"))
      (node (ref "C8") (pin "2") (pinfunction "2_2") (pintype "passive"))
      (node (ref "C9") (pin "2") (pinfunction "2_2") (pintype "passive"))
      (node (ref "IC1") (pin "1") (pinfunction "GND_1") (pintype "bidirectional"))
      (node (ref "IC2") (pin "1") (pinfunction "A0_1") (pintype "input"))
      (node (ref "IC2") (pin "2") (pinfunction "A1_2") (pintype "input"))
      (node (ref "IC2") (pin "3") (pinfunction "A2_3") (pintype "input"))
      (node (ref "IC2") (pin "4") (pinfunction "VSS_4") (pintype "passive"))
      (node (ref "IC3") (pin "18") (pinfunction "GND_18") (pintype "power_in"))
      (node (ref "IC3") (pin "21") (pinfunction "GND_21") (pintype "power_in"))
      (node (ref "IC3") (pin "25") (pinfunction "GND_25") (pintype "power_in"))
      (node (ref "IC3") (pin "7") (pinfunction "GND_7") (pintype "power_in"))
      (node (ref "IC4") (pin "13") (pinfunction "GND_3_13") (pintype "bidirectional"))
      (node (ref "IC4") (pin "18") (pinfunction "GND_4_18") (pintype "bidirectional"))
      (node (ref "IC4") (pin "23") (pinfunction "GND_5_23") (pintype "bidirectional"))
      (node (ref "IC4") (pin "28") (pinfunction "GND_6_28") (pintype "bidirectional"))
      (node (ref "IC4") (pin "3") (pinfunction "GND_1_3") (pintype "bidirectional"))
      (node (ref "IC4") (pin "33") (pinfunction "GND/AGND_33") (pintype "bidirectional"))
      (node (ref "IC4") (pin "38") (pinfunction "GND_7_38") (pintype "bidirectional"))
      (node (ref "IC4") (pin "8") (pinfunction "GND_2_8") (pintype "bidirectional"))
      (node (ref "IC8") (pin "1") (pinfunction "GND_1") (pintype "power_in"))
      (node (ref "J2") (pin "1") (pinfunction "1_1") (pintype "bidirectional"))
      (node (ref "R11") (pin "2") (pinfunction "2_2") (pintype "passive"))
      (node (ref "R31") (pin "2") (pinfunction "2_2") (pintype "passive"))
      (node (ref "R32") (pin "2") (pinfunction "2_2") (pintype "passive"))
      (node (ref "R33") (pin "2") (pinfunction "2_2") (pintype "passive"))
      (node (ref "R34") (pin "2") (pinfunction "2_2") (pintype "passive"))
      (node (ref "R35") (pin "2") (pinfunction "2_2") (pintype "passive"))
      (node (ref "R39") (pin "2") (pinfunction "2_2") (pintype "passive"))
      (node (ref "R40") (pin "1") (pinfunction "1_1") (pintype "passive"))
      (node (ref "R6") (pin "1") (pinfunction "1_1") (pintype "passive"))
      (node (ref "S1") (pin "2") (pinfunction "COM_1_2") (pintype "bidirectional"))
      (node (ref "S1") (pin "4") (pinfunction "COM_2_4") (pintype "bidirectional"))
      (node (ref "U$1") (pin "P$1") (pinfunction "/OE1_P$1") (pintype "input"))
      (node (ref "U$1") (pin "P$10") (pinfunction "GND_P$10") (pintype "power_in"))
      (node (ref "U$1") (pin "P$19") (pinfunction "/OE2_P$19") (pintype "input"))
      (node (ref "U$1") (pin "P$5") (pinfunction "A3_P$5") (pintype "input"))
      (node (ref "U$1") (pin "P$6") (pinfunction "A4_P$6") (pintype "input"))
      (node (ref "U$1") (pin "P$7") (pinfunction "A5_P$7") (pintype "input"))
      (node (ref "U$1") (pin "P$8") (pinfunction "A6_P$8") (pintype "input"))
      (node (ref "U$1") (pin "P$9") (pinfunction "A7_P$9") (pintype "input"))
      (node (ref "U$3") (pin "P$1") (pinfunction "/OE1_P$1") (pintype "input"))
      (node (ref "U$3") (pin "P$10") (pinfunction "GND_P$10") (pintype "power_in"))
      (node (ref "U$3") (pin "P$19") (pinfunction "/OE2_P$19") (pintype "input"))
      (node (ref "U1") (pin "14") (pinfunction "AGND_14") (pintype "passive"))
      (node (ref "U1") (pin "16") (pinfunction "AGND_16") (pintype "passive"))
      (node (ref "U1") (pin "19") (pinfunction "AGND_19") (pintype "passive"))
      (node (ref "U1") (pin "29") (pinfunction "GND_29") (pintype "passive"))
      (node (ref "U1") (pin "3") (pinfunction "AGND_3") (pintype "passive"))
      (node (ref "U1") (pin "48") (pinfunction "AGND_48") (pintype "passive"))
      (node (ref "U1") (pin "9") (pinfunction "AGND_9") (pintype "passive"))
      (node (ref "X1") (pin "1") (pinfunction "KL_1") (pintype "passive"))
      (node (ref "X10") (pin "1") (pinfunction "KL_1") (pintype "passive"))
      (node (ref "X11") (pin "1") (pinfunction "KL_1") (pintype "passive"))
      (node (ref "X12") (pin "1") (pinfunction "KL_1") (pintype "passive"))
      (node (ref "X13") (pin "4") (pinfunction "4_4") (pintype "passive"))
      (node (ref "X13") (pin "S1") (pinfunction "S1_S1") (pintype "passive"))
      (node (ref "X13") (pin "S2") (pinfunction "S2_S2") (pintype "passive"))
      (node (ref "X2") (pin "1") (pinfunction "KL_1") (pintype "passive"))
      (node (ref "X3") (pin "1") (pinfunction "KL_1") (pintype "passive"))
      (node (ref "X4") (pin "1") (pinfunction "KL_1") (pintype "passive"))
      (node (ref "X5") (pin "3") (pinfunction "KL_3") (pintype "passive"))
      (node (ref "X6") (pin "1") (pinfunction "KL_1") (pintype "passive"))
      (node (ref "X9") (pin "4") (pinfunction "4/NC_4") (pintype "input"))
      (node (ref "X9") (pin "5") (pinfunction "5/NC_5") (pintype "input"))
      (node (ref "X9") (pin "M1") (pinfunction "CGND_M1") (pintype "bidirectional"))
      (node (ref "X9") (pin "M2") (pinfunction "CGND2_M2") (pintype "bidirectional"))
    )
    (net (code "23") (name "HOME_SHUTTER_CLOSED") (class "Default")
      (node (ref "IC4") (pin "10") (pinfunction "I2C1_SCL_/SPI0_TX/GP7_10") (pintype "bidirectional"))
      (node (ref "U$3") (pin "P$17") (pinfunction "Y1_P$17") (pintype "output"))
    )
    (net (code "24") (name "HOME_SHUTTER_CLOSED-IN_EXT") (class "Default")
      (node (ref "R50") (pin "2") (pinfunction "2_2") (pintype "passive"))
      (node (ref "X1") (pin "2") (pinfunction "KL_2") (pintype "passive"))
    )
    (net (code "25") (name "HOME_SHUTTER_CLOSED_IN_5V") (class "Default")
      (node (ref "C46") (pin "1") (pinfunction "1_1") (pintype "passive"))
      (node (ref "R18") (pin "2") (pinfunction "2_2") (pintype "passive"))
      (node (ref "R50") (pin "1") (pinfunction "1_1") (pintype "passive"))
      (node (ref "U$3") (pin "P$3") (pinfunction "A1_P$3") (pintype "input"))
    )
    (net (code "26") (name "INT_N") (class "Default")
      (node (ref "IC4") (pin "32") (pinfunction "I2C1_SCL_/ADC1/GP_27_32") (pintype "bidirectional"))
      (node (ref "U1") (pin "36") (pinfunction "INT_N_36") (pintype "passive"))
    )
    (net (code "27") (name "LINK_ACK") (class "Default")
      (node (ref "U1") (pin "25") (pinfunction "LINKLED_25") (pintype "passive"))
      (node (ref "X9") (pin "10") (pinfunction "C-R_10") (pintype "passive"))
    )
    (net (code "28") (name "M_DIR") (class "Default")
      (node (ref "IC4") (pin "5") (pinfunction "I2C0_SCL_/SPI0_TX/GP3_5") (pintype "bidirectional"))
      (node (ref "U$1") (pin "P$3") (pinfunction "A1_P$3") (pintype "input"))
    )
    (net (code "29") (name "M_DIR_5V") (class "Default")
      (node (ref "R22") (pin "2") (pinfunction "2_2") (pintype "passive"))
      (node (ref "U$1") (pin "P$17") (pinfunction "Y1_P$17") (pintype "output"))
    )
    (net (code "30") (name "M_EN") (class "Default")
      (node (ref "IC4") (pin "4") (pinfunction "I2C1_SDA_/SPI0_SCK/GP2_4") (pintype "bidirectional"))
      (node (ref "U$1") (pin "P$2") (pinfunction "A0_P$2") (pintype "input"))
    )
    (net (code "31") (name "M_EN_5V") (class "Default")
      (node (ref "R12") (pin "2") (pinfunction "2_2") (pintype "passive"))
      (node (ref "U$1") (pin "P$18") (pinfunction "Y0_P$18") (pintype "output"))
    )
    (net (code "32") (name "M_STEP") (class "Default")
      (node (ref "IC4") (pin "27") (pinfunction "I2C0_SCL/GP21_27") (pintype "bidirectional"))
      (node (ref "U$1") (pin "P$4") (pinfunction "A2_P$4") (pintype "input"))
    )
    (net (code "33") (name "M_STEP_5V") (class "Default")
      (node (ref "R41") (pin "2") (pinfunction "2_2") (pintype "passive"))
      (node (ref "U$1") (pin "P$16") (pinfunction "Y2_P$16") (pintype "output"))
    )
    (net (code "34") (name "Net-(IC3-3V3OUT)") (class "Default")
      (node (ref "C8") (pin "1") (pinfunction "1_1") (pintype "passive"))
      (node (ref "IC3") (pin "17") (pinfunction "3V3OUT_17") (pintype "output"))
    )
    (net (code "35") (name "Net-(IC3-~{CTS})") (class "Default")
      (node (ref "IC3") (pin "11") (pinfunction "~{CTS}_11") (pintype "input"))
      (node (ref "IC3") (pin "3") (pinfunction "~{RTS}_3") (pintype "output"))
    )
    (net (code "36") (name "Net-(IC3-~{DCD})") (class "Default")
      (node (ref "IC3") (pin "10") (pinfunction "~{DCD}_10") (pintype "input"))
      (node (ref "IC3") (pin "2") (pinfunction "~{DTR}_2") (pintype "output"))
      (node (ref "IC3") (pin "9") (pinfunction "~{DSR}_9") (pintype "input"))
    )
    (net (code "37") (name "Net-(IC4-VBUS)") (class "Default")
      (node (ref "IC4") (pin "40") (pinfunction "VBUS_40") (pintype "bidirectional"))
      (node (ref "Q1") (pin "1") (pinfunction "G_1") (pintype "bidirectional"))
    )
    (net (code "38") (name "Net-(IC4-VSYS)") (class "Default")
      (node (ref "IC4") (pin "39") (pinfunction "VSYS_39") (pintype "bidirectional"))
      (node (ref "Q1") (pin "2") (pinfunction "S_2") (pintype "bidirectional"))
    )
    (net (code "39") (name "Net-(R2-Pad2)") (class "Default")
      (node (ref "R2") (pin "2") (pinfunction "2_2") (pintype "passive"))
      (node (ref "R7") (pin "1") (pinfunction "1_1") (pintype "passive"))
    )
    (net (code "40") (name "Net-(R7-Pad2)") (class "Default")
      (node (ref "R7") (pin "2") (pinfunction "2_2") (pintype "passive"))
      (node (ref "R8") (pin "1") (pinfunction "1_1") (pintype "passive"))
    )
    (net (code "41") (name "Net-(R10-Pad1)") (class "Default")
      (node (ref "R10") (pin "1") (pinfunction "1_1") (pintype "passive"))
      (node (ref "R8") (pin "2") (pinfunction "2_2") (pintype "passive"))
    )
    (net (code "42") (name "Net-(R31-Pad1)") (class "Default")
      (node (ref "R31") (pin "1") (pinfunction "1_1") (pintype "passive"))
      (node (ref "U1") (pin "38") (pinfunction "RSVD_38") (pintype "passive"))
    )
    (net (code "43") (name "Net-(R32-Pad1)") (class "Default")
      (node (ref "R32") (pin "1") (pinfunction "1_1") (pintype "passive"))
      (node (ref "U1") (pin "39") (pinfunction "RSVD_39") (pintype "passive"))
    )
    (net (code "44") (name "Net-(R33-Pad1)") (class "Default")
      (node (ref "R33") (pin "1") (pinfunction "1_1") (pintype "passive"))
      (node (ref "U1") (pin "40") (pinfunction "RSVD_40") (pintype "passive"))
    )
    (net (code "45") (name "Net-(R34-Pad1)") (class "Default")
      (node (ref "R34") (pin "1") (pinfunction "1_1") (pintype "passive"))
      (node (ref "U1") (pin "41") (pinfunction "RSVD_41") (pintype "passive"))
    )
    (net (code "46") (name "Net-(R35-Pad1)") (class "Default")
      (node (ref "R35") (pin "1") (pinfunction "1_1") (pintype "passive"))
      (node (ref "U1") (pin "42") (pinfunction "RSVD_42") (pintype "passive"))
    )
    (net (code "47") (name "Net-(R40-Pad2)") (class "Default")
      (node (ref "R40") (pin "2") (pinfunction "2_2") (pintype "passive"))
      (node (ref "U1") (pin "23") (pinfunction "RSVD_23") (pintype "passive"))
    )
    (net (code "48") (name "Net-(T1-B)") (class "Default")
      (node (ref "R12") (pin "1") (pinfunction "1_1") (pintype "passive"))
      (node (ref "T1") (pin "1") (pinfunction "B_1") (pintype "passive"))
    )
    (net (code "49") (name "Net-(T2-B)") (class "Default")
      (node (ref "R22") (pin "1") (pinfunction "1_1") (pintype "passive"))
      (node (ref "T2") (pin "1") (pinfunction "B_1") (pintype "passive"))
    )
    (net (code "50") (name "Net-(T3-B)") (class "Default")
      (node (ref "R41") (pin "1") (pinfunction "1_1") (pintype "passive"))
      (node (ref "T3") (pin "1") (pinfunction "B_1") (pintype "passive"))
    )
    (net (code "51") (name "Net-(U1-1V2O)") (class "Default")
      (node (ref "C18") (pin "2") (pinfunction "2_2") (pintype "passive"))
      (node (ref "U1") (pin "22") (pinfunction "1V2O_22") (pintype "passive"))
    )
    (net (code "52") (name "Net-(U1-EXRES1)") (class "Default")
      (node (ref "R39") (pin "1") (pinfunction "1_1") (pintype "passive"))
      (node (ref "U1") (pin "10") (pinfunction "EXRES1_10") (pintype "passive"))
    )
    (net (code "53") (name "Net-(U1-PMODE0)") (class "Default")
      (node (ref "R38") (pin "1") (pinfunction "1_1") (pintype "passive"))
      (node (ref "U1") (pin "45") (pinfunction "PMODE0_45") (pintype "passive"))
    )
    (net (code "54") (name "Net-(U1-PMODE1)") (class "Default")
      (node (ref "R37") (pin "1") (pinfunction "1_1") (pintype "passive"))
      (node (ref "U1") (pin "44") (pinfunction "PMODE1_44") (pintype "passive"))
    )
    (net (code "55") (name "Net-(U1-PMODE2)") (class "Default")
      (node (ref "R36") (pin "1") (pinfunction "1_1") (pintype "passive"))
      (node (ref "U1") (pin "43") (pinfunction "PMODE2_43") (pintype "passive"))
    )
    (net (code "56") (name "Net-(U1-TOCAP)") (class "Default")
      (node (ref "C19") (pin "2") (pinfunction "2_2") (pintype "passive"))
      (node (ref "U1") (pin "20") (pinfunction "TOCAP_20") (pintype "passive"))
    )
    (net (code "57") (name "Net-(X9-A-R)") (class "Default")
      (node (ref "R29") (pin "1") (pinfunction "1_1") (pintype "passive"))
      (node (ref "X9") (pin "9") (pinfunction "A-R_9") (pintype "passive"))
    )
    (net (code "58") (name "Net-(X9-AL)") (class "Default")
      (node (ref "R28") (pin "1") (pinfunction "1_1") (pintype "passive"))
      (node (ref "X9") (pin "12") (pinfunction "AL_12") (pintype "passive"))
    )
    (net (code "59") (name "Net-(X9-CR)") (class "Default")
      (node (ref "C22") (pin "1") (pinfunction "1_1") (pintype "passive"))
      (node (ref "R26") (pin "2") (pinfunction "2_2") (pintype "passive"))
      (node (ref "R27") (pin "2") (pinfunction "2_2") (pintype "passive"))
      (node (ref "X9") (pin "6") (pinfunction "CR_6") (pintype "input"))
    )
    (net (code "60") (name "Net-(X9-CT)") (class "Default")
      (node (ref "C10") (pin "1") (pinfunction "1_1") (pintype "passive"))
      (node (ref "R23") (pin "1") (pinfunction "1_1") (pintype "passive"))
      (node (ref "X9") (pin "3") (pinfunction "CT_3") (pintype "input"))
    )
    (net (code "61") (name "Net-(X9-RD+)") (class "Default")
      (node (ref "C15") (pin "2") (pinfunction "2_2") (pintype "passive"))
      (node (ref "X9") (pin "7") (pinfunction "RD+_7") (pintype "input"))
    )
    (net (code "62") (name "Net-(X9-RD-)") (class "Default")
      (node (ref "C21") (pin "2") (pinfunction "2_2") (pintype "passive"))
      (node (ref "X9") (pin "8") (pinfunction "RD-_8") (pintype "input"))
    )
    (net (code "63") (name "RESET") (class "Default")
      (node (ref "IC4") (pin "30") (pinfunction "RUN_30") (pintype "bidirectional"))
      (node (ref "S1") (pin "3") (pinfunction "NO_2_3") (pintype "bidirectional"))
    )
    (net (code "64") (name "RG-11") (class "Default")
      (node (ref "IC4") (pin "17") (pinfunction "UART0_RX/I2C0_SCL_/SPI1_CSN/GP13_17") (pintype "bidirectional"))
      (node (ref "U$3") (pin "P$13") (pinfunction "Y5_P$13") (pintype "output"))
    )
    (net (code "65") (name "RG-11-IN_5V") (class "Default")
      (node (ref "C1") (pin "1") (pinfunction "1_1") (pintype "passive"))
      (node (ref "R4") (pin "1") (pinfunction "1_1") (pintype "passive"))
      (node (ref "R5") (pin "1") (pinfunction "1_1") (pintype "passive"))
      (node (ref "U$3") (pin "P$7") (pinfunction "A5_P$7") (pintype "input"))
    )
    (net (code "66") (name "RG-11-IN_EXT") (class "Default")
      (node (ref "R5") (pin "2") (pinfunction "2_2") (pintype "passive"))
      (node (ref "X5") (pin "2") (pinfunction "KL_2") (pintype "passive"))
    )
    (net (code "67") (name "RX") (class "Default")
      (node (ref "IC4") (pin "1") (pinfunction "UART0_TX/I2C0_SDA_/SPI0_RX/GP0_1") (pintype "bidirectional"))
    )
    (net (code "68") (name "RX2") (class "Default")
      (node (ref "IC3") (pin "1") (pinfunction "TXD_1") (pintype "output"))
      (node (ref "IC4") (pin "12") (pinfunction "UART1_RX/I2C0_SCL_/SPI1_CSN/GP9_12") (pintype "bidirectional"))
    )
    (net (code "69") (name "RXN") (class "Default")
      (node (ref "C21") (pin "1") (pinfunction "1_1") (pintype "passive"))
      (node (ref "R26") (pin "1") (pinfunction "1_1") (pintype "passive"))
      (node (ref "U1") (pin "5") (pinfunction "RXN_5") (pintype "passive"))
    )
    (net (code "70") (name "RXP") (class "Default")
      (node (ref "C15") (pin "1") (pinfunction "1_1") (pintype "passive"))
      (node (ref "R27") (pin "1") (pinfunction "1_1") (pintype "passive"))
      (node (ref "U1") (pin "6") (pinfunction "RXP_6") (pintype "passive"))
    )
    (net (code "71") (name "SCL") (class "Default")
      (node (ref "IC2") (pin "6") (pinfunction "SCL_6") (pintype "input"))
      (node (ref "IC4") (pin "7") (pinfunction "UART1_RX/I2C0_SCL_/SPI0_CSN/GP5_7") (pintype "bidirectional"))
      (node (ref "R1") (pin "1") (pinfunction "1_1") (pintype "passive"))
    )
    (net (code "72") (name "SCLK") (class "Default")
      (node (ref "IC4") (pin "24") (pinfunction "I2C1_SDA/_SPI0_SCK/GP18_24") (pintype "bidirectional"))
      (node (ref "U1") (pin "33") (pinfunction "SCLK_33") (pintype "passive"))
    )
    (net (code "73") (name "SDA") (class "Default")
      (node (ref "IC2") (pin "5") (pinfunction "SDA_5") (pintype "bidirectional"))
      (node (ref "IC4") (pin "6") (pinfunction "UART1_TX/I2C0_SDA_/SPI0_RX/GP4_6") (pintype "bidirectional"))
      (node (ref "R3") (pin "1") (pinfunction "1_1") (pintype "passive"))
    )
    (net (code "74") (name "SDI") (class "Default")
      (node (ref "IC4") (pin "21") (pinfunction "UART0_TX/I2C0_SDA_/SPI0_RX_/GP16_21") (pintype "bidirectional"))
      (node (ref "U1") (pin "34") (pinfunction "MISO_34") (pintype "passive"))
    )
    (net (code "75") (name "SDO") (class "Default")
      (node (ref "IC4") (pin "25") (pinfunction "I2C1_SCL/_SPI0_TX/GP19_25") (pintype "bidirectional"))
      (node (ref "U1") (pin "35") (pinfunction "MOSI_35") (pintype "passive"))
    )
    (net (code "76") (name "SHUTTER_OPENED") (class "Default")
      (node (ref "IC4") (pin "19") (pinfunction "I2C1_SDA/SPI1_SCK/GP14_19") (pintype "bidirectional"))
      (node (ref "U$3") (pin "P$12") (pinfunction "Y6_P$12") (pintype "output"))
    )
    (net (code "77") (name "SHUTTER_OPENED-IN_EXT") (class "Default")
      (node (ref "R48") (pin "2") (pinfunction "2_2") (pintype "passive"))
      (node (ref "X3") (pin "2") (pinfunction "KL_2") (pintype "passive"))
    )
    (net (code "78") (name "SHUTTER_OPENED_IN_5V") (class "Default")
      (node (ref "C44") (pin "1") (pinfunction "1_1") (pintype "passive"))
      (node (ref "R17") (pin "2") (pinfunction "2_2") (pintype "passive"))
      (node (ref "R48") (pin "1") (pinfunction "1_1") (pintype "passive"))
      (node (ref "U$3") (pin "P$8") (pinfunction "A6_P$8") (pintype "input"))
    )
    (net (code "79") (name "SPARE1") (class "Default")
      (node (ref "IC4") (pin "9") (pinfunction "I2C1_SDA_/SPI0_SCK/GP6_9") (pintype "bidirectional"))
      (node (ref "U$3") (pin "P$18") (pinfunction "Y0_P$18") (pintype "output"))
    )
    (net (code "80") (name "SPARE1-IN_EXT") (class "Default")
      (node (ref "R45") (pin "2") (pinfunction "2_2") (pintype "passive"))
      (node (ref "X8") (pin "1") (pinfunction "KL_1") (pintype "passive"))
    )
    (net (code "81") (name "SPARE1_IN_5V") (class "Default")
      (node (ref "C41") (pin "1") (pinfunction "1_1") (pintype "passive"))
      (node (ref "R21") (pin "2") (pinfunction "2_2") (pintype "passive"))
      (node (ref "R45") (pin "1") (pinfunction "1_1") (pintype "passive"))
      (node (ref "U$3") (pin "P$2") (pinfunction "A0_P$2") (pintype "input"))
    )
    (net (code "82") (name "SPARE2") (class "Default")
      (node (ref "IC4") (pin "16") (pinfunction "UART0_TX/I2C0_SDA_/SPI1_RX_/GP12_16") (pintype "bidirectional"))
      (node (ref "U$3") (pin "P$14") (pinfunction "Y4_P$14") (pintype "output"))
    )
    (net (code "83") (name "SPARE2-IN_EXT") (class "Default")
      (node (ref "R49") (pin "2") (pinfunction "2_2") (pintype "passive"))
      (node (ref "X8") (pin "2") (pinfunction "KL_2") (pintype "passive"))
    )
    (net (code "84") (name "SPARE2_IN_5V") (class "Default")
      (node (ref "C45") (pin "1") (pinfunction "1_1") (pintype "passive"))
      (node (ref "R49") (pin "1") (pinfunction "1_1") (pintype "passive"))
      (node (ref "R9") (pin "2") (pinfunction "2_2") (pintype "passive"))
      (node (ref "U$3") (pin "P$6") (pinfunction "A4_P$6") (pintype "input"))
    )
    (net (code "85") (name "STEP_5V_OUT") (class "Default")
      (node (ref "T3") (pin "2") (pinfunction "E_2") (pintype "passive"))
      (node (ref "X6") (pin "2") (pinfunction "KL_2") (pintype "passive"))
    )
    (net (code "86") (name "TX") (class "Default")
      (node (ref "IC4") (pin "2") (pinfunction "UART0_RX/I2C0_SCL_/SPI0_CSN/GP1_2") (pintype "bidirectional"))
    )
    (net (code "87") (name "TX2") (class "Default")
      (node (ref "IC3") (pin "5") (pinfunction "RXD_5") (pintype "input"))
      (node (ref "IC4") (pin "11") (pinfunction "UART1_TX/I2C0_SDA_/SPI1_RX/GP8_11") (pintype "bidirectional"))
    )
    (net (code "88") (name "TXN") (class "Default")
      (node (ref "R25") (pin "1") (pinfunction "1_1") (pintype "passive"))
      (node (ref "U1") (pin "1") (pinfunction "TXN_1") (pintype "passive"))
      (node (ref "X9") (pin "2") (pinfunction "TD-_2") (pintype "input"))
    )
    (net (code "89") (name "TXP") (class "Default")
      (node (ref "R24") (pin "1") (pinfunction "1_1") (pintype "passive"))
      (node (ref "U1") (pin "2") (pinfunction "TXP_2") (pintype "passive"))
      (node (ref "X9") (pin "1") (pinfunction "TD+_1") (pintype "input"))
    )
    (net (code "90") (name "USBD_N") (class "Default")
      (node (ref "IC3") (pin "16") (pinfunction "USBDM_16") (pintype "bidirectional"))
      (node (ref "X13") (pin "2") (pinfunction "2_2") (pintype "passive"))
    )
    (net (code "91") (name "USBD_P") (class "Default")
      (node (ref "IC3") (pin "15") (pinfunction "USBDP_15") (pintype "bidirectional"))
      (node (ref "X13") (pin "3") (pinfunction "3_3") (pintype "passive"))
    )
    (net (code "92") (name "USB_VCC") (class "Default")
      (node (ref "X13") (pin "1") (pinfunction "1_1") (pintype "passive"))
    )
    (net (code "93") (name "VCC") (class "Default")
      (node (ref "C23") (pin "1") (pinfunction "1_1") (pintype "passive"))
      (node (ref "C28") (pin "1") (pinfunction "1_1") (pintype "passive"))
      (node (ref "C6") (pin "1") (pinfunction "1_1") (pintype "passive"))
      (node (ref "C7") (pin "1") (pinfunction "1_1") (pintype "passive"))
      (node (ref "IC1") (pin "2") (pinfunction "VOUT_1_2") (pintype "bidirectional"))
      (node (ref "IC1") (pin "4") (pinfunction "VOUT_2_4") (pintype "bidirectional"))
      (node (ref "IC3") (pin "20") (pinfunction "VCC_20") (pintype "power_in"))
      (node (ref "IC8") (pin "3") (pinfunction "VIN_3") (pintype "input"))
      (node (ref "Q1") (pin "3") (pinfunction "D_3") (pintype "bidirectional"))
      (node (ref "R15") (pin "1") (pinfunction "1_1") (pintype "passive"))
      (node (ref "R16") (pin "1") (pinfunction "1_1") (pintype "passive"))
      (node (ref "R17") (pin "1") (pinfunction "1_1") (pintype "passive"))
      (node (ref "R18") (pin "1") (pinfunction "1_1") (pintype "passive"))
      (node (ref "R20") (pin "2") (pinfunction "2_2") (pintype "passive"))
      (node (ref "R21") (pin "1") (pinfunction "1_1") (pintype "passive"))
      (node (ref "R4") (pin "2") (pinfunction "2_2") (pintype "passive"))
      (node (ref "R9") (pin "1") (pinfunction "1_1") (pintype "passive"))
      (node (ref "T1") (pin "3") (pinfunction "C_3") (pintype "passive"))
      (node (ref "T2") (pin "3") (pinfunction "C_3") (pintype "passive"))
      (node (ref "T3") (pin "3") (pinfunction "C_3") (pintype "passive"))
      (node (ref "U$1") (pin "P$20") (pinfunction "VCC_P$20") (pintype "power_in"))
      (node (ref "X10") (pin "3") (pinfunction "KL_3") (pintype "passive"))
      (node (ref "X2") (pin "3") (pinfunction "KL_3") (pintype "passive"))
      (node (ref "X6") (pin "3") (pinfunction "KL_3") (pintype "passive"))
    )
    (net (code "94") (name "VPIN") (class "Default")
      (node (ref "IC4") (pin "31") (pinfunction "I2C1_SDA/ADC0/GP26_31") (pintype "bidirectional"))
      (node (ref "R2") (pin "1") (pinfunction "1_1") (pintype "passive"))
      (node (ref "R6") (pin "2") (pinfunction "2_2") (pintype "passive"))
    )
    (net (code "95") (name "XBEE_RESET") (class "Default")
      (node (ref "IC4") (pin "29") (pinfunction "GP22_29") (pintype "bidirectional"))
    )
    (net (code "96") (name "XI") (class "Default")
      (node (ref "25MHZ") (pin "3") (pinfunction "FO_3") (pintype "output"))
      (node (ref "U1") (pin "30") (pinfunction "XI/CLKIN_30") (pintype "passive"))
    )
    (net (code "97") (name "XO") (class "Default")
      (node (ref "U1") (pin "31") (pinfunction "XO_31") (pintype "passive"))
    )
    (net (code "98") (name "unconnected-(IC2-WP-Pad7)") (class "Default")
      (node (ref "IC2") (pin "7") (pinfunction "WP_7") (pintype "input"))
    )
    (net (code "99") (name "unconnected-(IC3-CBUS0-Pad23)") (class "Default")
      (node (ref "IC3") (pin "23") (pinfunction "CBUS0_23") (pintype "bidirectional"))
    )
    (net (code "100") (name "unconnected-(IC3-CBUS1-Pad22)") (class "Default")
      (node (ref "IC3") (pin "22") (pinfunction "CBUS1_22") (pintype "bidirectional"))
    )
    (net (code "101") (name "unconnected-(IC3-CBUS2-Pad13)") (class "Default")
      (node (ref "IC3") (pin "13") (pinfunction "CBUS2_13") (pintype "bidirectional"))
    )
    (net (code "102") (name "unconnected-(IC3-CBUS3-Pad14)") (class "Default")
      (node (ref "IC3") (pin "14") (pinfunction "CBUS3_14") (pintype "bidirectional"))
    )
    (net (code "103") (name "unconnected-(IC3-CBUS4-Pad12)") (class "Default")
      (node (ref "IC3") (pin "12") (pinfunction "CBUS4_12") (pintype "bidirectional"))
    )
    (net (code "104") (name "unconnected-(IC3-OSCI-Pad27)") (class "Default")
      (node (ref "IC3") (pin "27") (pinfunction "OSCI_27") (pintype "input"))
    )
    (net (code "105") (name "unconnected-(IC3-OSCO-Pad28)") (class "Default")
      (node (ref "IC3") (pin "28") (pinfunction "OSCO_28") (pintype "output"))
    )
    (net (code "106") (name "unconnected-(IC3-TEST-Pad26)") (class "Default")
      (node (ref "IC3") (pin "26") (pinfunction "TEST_26") (pintype "input"))
    )
    (net (code "107") (name "unconnected-(IC3-~{RI}-Pad6)") (class "Default")
      (node (ref "IC3") (pin "6") (pinfunction "~{RI}_6") (pintype "input"))
    )
    (net (code "108") (name "unconnected-(J2-Pad3)") (class "Default")
      (node (ref "J2") (pin "3") (pinfunction "3_3") (pintype "bidirectional"))
    )
    (net (code "109") (name "unconnected-(J2-Pad4)") (class "Default")
      (node (ref "J2") (pin "4") (pinfunction "4_4") (pintype "bidirectional"))
    )
    (net (code "110") (name "unconnected-(S1-NO_1-Pad1)") (class "Default")
      (node (ref "S1") (pin "1") (pinfunction "NO_1_1") (pintype "bidirectional"))
    )
    (net (code "111") (name "unconnected-(U$1A-Y3-PadP$15)") (class "Default")
      (node (ref "U$1") (pin "P$15") (pinfunction "Y3_P$15") (pintype "output"))
    )
    (net (code "112") (name "unconnected-(U$1A-Y4-PadP$14)") (class "Default")
      (node (ref "U$1") (pin "P$14") (pinfunction "Y4_P$14") (pintype "output"))
    )
    (net (code "113") (name "unconnected-(U$1A-Y5-PadP$13)") (class "Default")
      (node (ref "U$1") (pin "P$13") (pinfunction "Y5_P$13") (pintype "output"))
    )
    (net (code "114") (name "unconnected-(U$1A-Y6-PadP$12)") (class "Default")
      (node (ref "U$1") (pin "P$12") (pinfunction "Y6_P$12") (pintype "output"))
    )
    (net (code "115") (name "unconnected-(U$1A-Y7-PadP$11)") (class "Default")
      (node (ref "U$1") (pin "P$11") (pinfunction "Y7_P$11") (pintype "output"))
    )
    (net (code "116") (name "unconnected-(U1-DNC-Pad7)") (class "Default")
      (node (ref "U1") (pin "7") (pinfunction "DNC_7") (pintype "passive"))
    )
    (net (code "117") (name "unconnected-(U1-DUPLED-Pad26)") (class "Default")
      (node (ref "U1") (pin "26") (pinfunction "DUPLED_26") (pintype "passive"))
    )
    (net (code "118") (name "unconnected-(U1-NC-Pad12)") (class "Default")
      (node (ref "U1") (pin "12") (pinfunction "NC_12") (pintype "passive"))
    )
    (net (code "119") (name "unconnected-(U1-NC-Pad13)") (class "Default")
      (node (ref "U1") (pin "13") (pinfunction "NC_13") (pintype "passive"))
    )
    (net (code "120") (name "unconnected-(U1-NC-Pad46)") (class "Default")
      (node (ref "U1") (pin "46") (pinfunction "NC_46") (pintype "passive"))
    )
    (net (code "121") (name "unconnected-(U1-NC-Pad47)") (class "Default")
      (node (ref "U1") (pin "47") (pinfunction "NC_47") (pintype "passive"))
    )
    (net (code "122") (name "unconnected-(U1-SPDLED-Pad24)") (class "Default")
      (node (ref "U1") (pin "24") (pinfunction "SPDLED_24") (pintype "passive"))
    )
    (net (code "123") (name "unconnected-(U1-VBG-Pad18)") (class "Default")
      (node (ref "U1") (pin "18") (pinfunction "VBG_18") (pintype "passive"))
    )
  )
)
